# alphanewt_v1_3.net
KiCad netlist of a schematic drawn in EAGLE
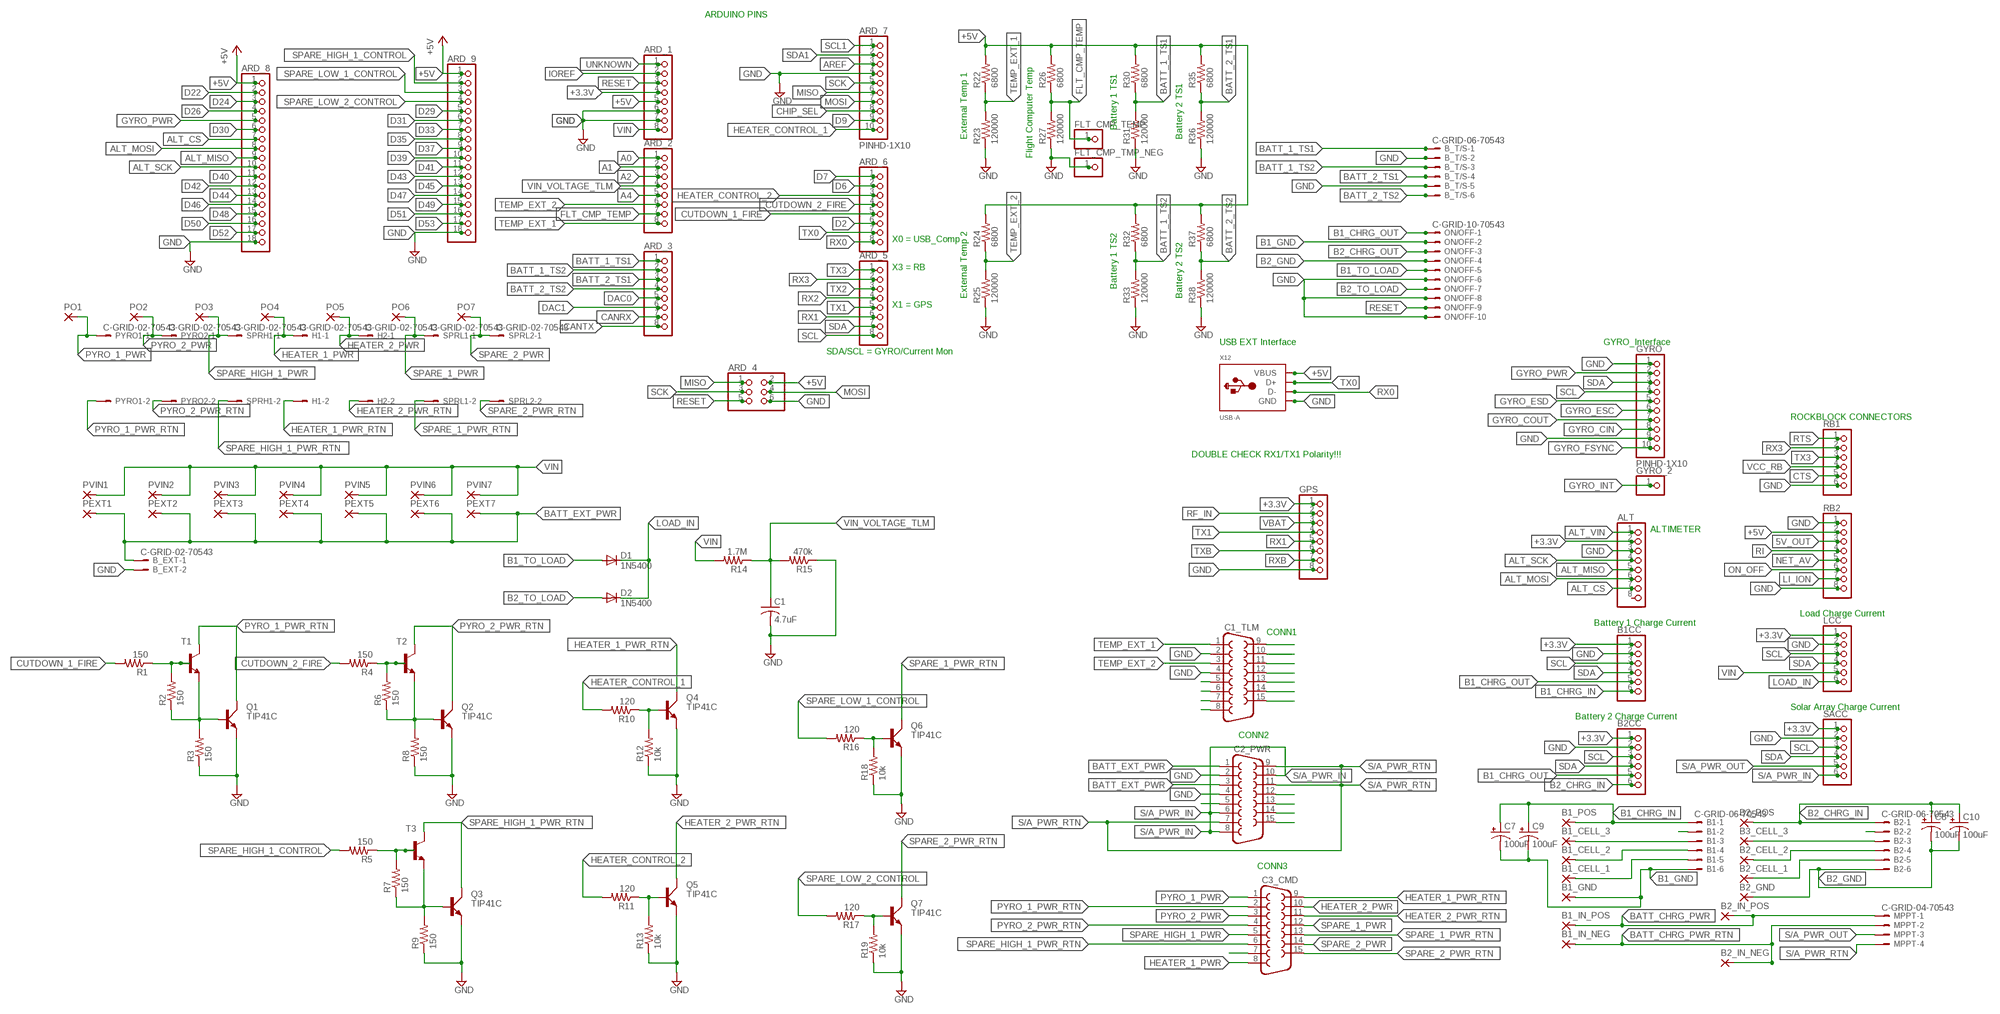
[diagram p0: schematic, sheet 1]

(export (version "E")
  (design (tool "Eeschema 10.0.6"))
  (components
    (comp (ref "ALT")
      (value "PINHD-1X8BIG")
      (footprint "eagle-import:1X08-BIG")
      (libsource (lib "eagle-import") (part "PINHD-1X8BIG"))
    )
    (comp (ref "ARD_1")
      (value "PINHD-1X8BIG")
      (footprint "eagle-import:1X08-BIG")
      (libsource (lib "eagle-import") (part "PINHD-1X8BIG"))
    )
    (comp (ref "ARD_2")
      (value "PINHD-1X8BIG")
      (footprint "eagle-import:1X08-BIG")
      (libsource (lib "eagle-import") (part "PINHD-1X8BIG"))
    )
    (comp (ref "ARD_3")
      (value "PINHD-1X8BIG")
      (footprint "eagle-import:1X08-BIG")
      (libsource (lib "eagle-import") (part "PINHD-1X8BIG"))
    )
    (comp (ref "ARD_4")
      (value "PINHD-2X3")
      (footprint "eagle-import:2X03")
      (libsource (lib "eagle-import") (part "PINHD-2X3"))
    )
    (comp (ref "ARD_5")
      (value "PINHD-1X8BIG")
      (footprint "eagle-import:1X08-BIG")
      (libsource (lib "eagle-import") (part "PINHD-1X8BIG"))
    )
    (comp (ref "ARD_6")
      (value "PINHD-1X8BIG")
      (footprint "eagle-import:1X08-BIG")
      (libsource (lib "eagle-import") (part "PINHD-1X8BIG"))
    )
    (comp (ref "ARD_7")
      (value "PINHD-1X10")
      (footprint "eagle-import:1X10-BIG")
      (libsource (lib "eagle-import") (part "PINHD-1X10"))
    )
    (comp (ref "ARD_8")
      (value "PINHD-1X18-BIG")
      (footprint "eagle-import:1X18-BIG")
      (libsource (lib "eagle-import") (part "PINHD-1X18-BIG"))
    )
    (comp (ref "ARD_9")
      (value "PINHD-1X18-BIG")
      (footprint "eagle-import:1X18-BIG")
      (libsource (lib "eagle-import") (part "PINHD-1X18-BIG"))
    )
    (comp (ref "B1")
      (value "C-GRID-06-70543")
      (footprint "eagle-import:70543-06")
      (fields
        (field (name "MF") "MOLEX")
        (field (name "MPN") "70543-0005")
        (field (name "OC_NEWARK") "59H2647")
      )
      (libsource (lib "eagle-import") (part "C-GRID-06-70543"))
    )
    (comp (ref "B1CC")
      (value "PINHD-1X6B")
      (footprint "eagle-import:1X06-BIG")
      (libsource (lib "eagle-import") (part "PINHD-1X6B"))
    )
    (comp (ref "B1_CELL_1")
      (value "SMD5")
      (footprint "eagle-import:SMD2,54-5,08")
      (libsource (lib "eagle-import") (part "SMD5"))
    )
    (comp (ref "B1_CELL_2")
      (value "SMD5")
      (footprint "eagle-import:SMD2,54-5,08")
      (libsource (lib "eagle-import") (part "SMD5"))
    )
    (comp (ref "B1_CELL_3")
      (value "SMD5")
      (footprint "eagle-import:SMD2,54-5,08")
      (libsource (lib "eagle-import") (part "SMD5"))
    )
    (comp (ref "B1_GND")
      (value "SMD5")
      (footprint "eagle-import:SMD2,54-5,08")
      (libsource (lib "eagle-import") (part "SMD5"))
    )
    (comp (ref "B1_IN_NEG")
      (value "SMD5")
      (footprint "eagle-import:SMD2,54-5,08")
      (libsource (lib "eagle-import") (part "SMD5"))
    )
    (comp (ref "B1_IN_POS")
      (value "SMD5")
      (footprint "eagle-import:SMD2,54-5,08")
      (libsource (lib "eagle-import") (part "SMD5"))
    )
    (comp (ref "B1_POS")
      (value "SMD5")
      (footprint "eagle-import:SMD2,54-5,08")
      (libsource (lib "eagle-import") (part "SMD5"))
    )
    (comp (ref "B2")
      (value "C-GRID-06-70543")
      (footprint "eagle-import:70543-06")
      (fields
        (field (name "MF") "MOLEX")
        (field (name "MPN") "70543-0005")
        (field (name "OC_NEWARK") "59H2647")
      )
      (libsource (lib "eagle-import") (part "C-GRID-06-70543"))
    )
    (comp (ref "B2CC")
      (value "PINHD-1X6B")
      (footprint "eagle-import:1X06-BIG")
      (libsource (lib "eagle-import") (part "PINHD-1X6B"))
    )
    (comp (ref "B2_CELL_1")
      (value "SMD5")
      (footprint "eagle-import:SMD2,54-5,08")
      (libsource (lib "eagle-import") (part "SMD5"))
    )
    (comp (ref "B2_CELL_2")
      (value "SMD5")
      (footprint "eagle-import:SMD2,54-5,08")
      (libsource (lib "eagle-import") (part "SMD5"))
    )
    (comp (ref "B2_GND")
      (value "SMD5")
      (footprint "eagle-import:SMD2,54-5,08")
      (libsource (lib "eagle-import") (part "SMD5"))
    )
    (comp (ref "B2_IN_NEG")
      (value "SMD5")
      (footprint "eagle-import:SMD2,54-5,08")
      (libsource (lib "eagle-import") (part "SMD5"))
    )
    (comp (ref "B2_IN_POS")
      (value "SMD5")
      (footprint "eagle-import:SMD2,54-5,08")
      (libsource (lib "eagle-import") (part "SMD5"))
    )
    (comp (ref "B2_POS")
      (value "SMD5")
      (footprint "eagle-import:SMD2,54-5,08")
      (libsource (lib "eagle-import") (part "SMD5"))
    )
    (comp (ref "B3_CELL_3")
      (value "SMD5")
      (footprint "eagle-import:SMD2,54-5,08")
      (libsource (lib "eagle-import") (part "SMD5"))
    )
    (comp (ref "B_EXT")
      (value "C-GRID-02-70543")
      (footprint "eagle-import:70543-02")
      (fields
        (field (name "MF") "MOLEX")
        (field (name "MPN") "70543-0001")
        (field (name "OC_NEWARK") "59H2645")
      )
      (libsource (lib "eagle-import") (part "C-GRID-02-70543"))
    )
    (comp (ref "B_T/S")
      (value "C-GRID-06-70543")
      (footprint "eagle-import:70543-06")
      (fields
        (field (name "MF") "MOLEX")
        (field (name "MPN") "70543-0005")
        (field (name "OC_NEWARK") "59H2647")
      )
      (libsource (lib "eagle-import") (part "C-GRID-06-70543"))
    )
    (comp (ref "C1")
      (value "4.7uF")
      (footprint "eagle-import:C0805K")
      (fields (field (name "MPN") "C2012X6S1H475K125AC"))
      (libsource (lib "eagle-import") (part "C-USC0805K"))
    )
    (comp (ref "C1_TLM")
      (value "F15HP")
      (footprint "eagle-import:F15HP")
      (fields (field (name "MPN") "5504F1-15S-02A-03"))
      (libsource (lib "eagle-import") (part "F15HP"))
    )
    (comp (ref "C2_PWR")
      (value "F15HP")
      (footprint "eagle-import:F15HP")
      (fields (field (name "MPN") "5504F1-15S-02A-03"))
      (libsource (lib "eagle-import") (part "F15HP"))
    )
    (comp (ref "C3_CMD")
      (value "F15HP")
      (footprint "eagle-import:F15HP")
      (fields (field (name "MPN") "5504F1-15S-02A-03"))
      (libsource (lib "eagle-import") (part "F15HP"))
    )
    (comp (ref "C7")
      (value "100uF")
      (footprint "eagle-import:CT7343")
      (fields (field (name "MPN") "TCN4337M020R0100"))
      (libsource (lib "eagle-import") (part "CPOL-USCT7343"))
    )
    (comp (ref "C8")
      (value "100uF")
      (footprint "eagle-import:CT7343")
      (fields (field (name "MPN") "TCN4337M020R0100"))
      (libsource (lib "eagle-import") (part "CPOL-USCT7343"))
    )
    (comp (ref "C9")
      (value "100uF")
      (footprint "eagle-import:CT7343")
      (fields (field (name "MPN") "TCN4337M020R0100"))
      (libsource (lib "eagle-import") (part "CPOL-USCT7343"))
    )
    (comp (ref "C10")
      (value "100uF")
      (footprint "eagle-import:CT7343")
      (fields (field (name "MPN") "TCN4337M020R0100"))
      (libsource (lib "eagle-import") (part "CPOL-USCT7343"))
    )
    (comp (ref "D1")
      (value "1N5400")
      (footprint "eagle-import:DO201-15")
      (fields (field (name "MPN") "1N5400-E3/54"))
      (libsource (lib "eagle-import") (part "1N5400"))
    )
    (comp (ref "D2")
      (value "1N5400")
      (footprint "eagle-import:DO201-15")
      (fields (field (name "MPN") "1N5400-E3/54"))
      (libsource (lib "eagle-import") (part "1N5400"))
    )
    (comp (ref "FLT_CMP_TEMP")
      (value "PINHD-1X1")
      (footprint "eagle-import:1X01")
      (libsource (lib "eagle-import") (part "PINHD-1X1"))
    )
    (comp (ref "FLT_CMP_TMP_NEG")
      (value "PINHD-1X1")
      (footprint "eagle-import:1X01")
      (libsource (lib "eagle-import") (part "PINHD-1X1"))
    )
    (comp (ref "GPS")
      (value "PINHD-1X8BIG")
      (footprint "eagle-import:1X08-BIG")
      (libsource (lib "eagle-import") (part "PINHD-1X8BIG"))
    )
    (comp (ref "GYRO")
      (value "PINHD-1X10")
      (footprint "eagle-import:1X10-BIG")
      (libsource (lib "eagle-import") (part "PINHD-1X10"))
    )
    (comp (ref "GYRO_2")
      (value "PINHD-1X1")
      (footprint "eagle-import:1X01")
      (libsource (lib "eagle-import") (part "PINHD-1X1"))
    )
    (comp (ref "H1")
      (value "C-GRID-02-70543")
      (footprint "eagle-import:70543-02")
      (fields
        (field (name "MF") "MOLEX")
        (field (name "MPN") "70543-0001")
        (field (name "OC_NEWARK") "59H2645")
      )
      (libsource (lib "eagle-import") (part "C-GRID-02-70543"))
    )
    (comp (ref "H2")
      (value "C-GRID-02-70543")
      (footprint "eagle-import:70543-02")
      (fields
        (field (name "MF") "MOLEX")
        (field (name "MPN") "70543-0001")
        (field (name "OC_NEWARK") "59H2645")
      )
      (libsource (lib "eagle-import") (part "C-GRID-02-70543"))
    )
    (comp (ref "LCC")
      (value "PINHD-1X6B")
      (footprint "eagle-import:1X06-BIG")
      (libsource (lib "eagle-import") (part "PINHD-1X6B"))
    )
    (comp (ref "MPPT")
      (value "C-GRID-04-70543")
      (footprint "eagle-import:70543-04")
      (fields
        (field (name "MF") "MOLEX")
        (field (name "MPN") "70543-0038")
        (field (name "OC_NEWARK") "59H2665")
      )
      (libsource (lib "eagle-import") (part "C-GRID-04-70543"))
    )
    (comp (ref "ON/OFF")
      (value "C-GRID-10-70543")
      (footprint "eagle-import:70543-10")
      (fields
        (field (name "MF") "MOLEX")
        (field (name "MPN") "70543-0009")
        (field (name "OC_NEWARK") "59H2651")
      )
      (libsource (lib "eagle-import") (part "C-GRID-10-70543"))
    )
    (comp (ref "PEXT1")
      (value "SMD2")
      (footprint "eagle-import:SMD1,27-2,54")
      (libsource (lib "eagle-import") (part "SMD2"))
    )
    (comp (ref "PEXT2")
      (value "SMD2")
      (footprint "eagle-import:SMD1,27-2,54")
      (libsource (lib "eagle-import") (part "SMD2"))
    )
    (comp (ref "PEXT3")
      (value "SMD2")
      (footprint "eagle-import:SMD1,27-2,54")
      (libsource (lib "eagle-import") (part "SMD2"))
    )
    (comp (ref "PEXT4")
      (value "SMD2")
      (footprint "eagle-import:SMD1,27-2,54")
      (libsource (lib "eagle-import") (part "SMD2"))
    )
    (comp (ref "PEXT5")
      (value "SMD2")
      (footprint "eagle-import:SMD1,27-2,54")
      (libsource (lib "eagle-import") (part "SMD2"))
    )
    (comp (ref "PEXT6")
      (value "SMD2")
      (footprint "eagle-import:SMD1,27-2,54")
      (libsource (lib "eagle-import") (part "SMD2"))
    )
    (comp (ref "PEXT7")
      (value "SMD2")
      (footprint "eagle-import:SMD1,27-2,54")
      (libsource (lib "eagle-import") (part "SMD2"))
    )
    (comp (ref "PO1")
      (value "SMD2")
      (footprint "eagle-import:SMD1,27-2,54")
      (libsource (lib "eagle-import") (part "SMD2"))
    )
    (comp (ref "PO2")
      (value "SMD2")
      (footprint "eagle-import:SMD1,27-2,54")
      (libsource (lib "eagle-import") (part "SMD2"))
    )
    (comp (ref "PO3")
      (value "SMD2")
      (footprint "eagle-import:SMD1,27-2,54")
      (libsource (lib "eagle-import") (part "SMD2"))
    )
    (comp (ref "PO4")
      (value "SMD2")
      (footprint "eagle-import:SMD1,27-2,54")
      (libsource (lib "eagle-import") (part "SMD2"))
    )
    (comp (ref "PO5")
      (value "SMD2")
      (footprint "eagle-import:SMD1,27-2,54")
      (libsource (lib "eagle-import") (part "SMD2"))
    )
    (comp (ref "PO6")
      (value "SMD2")
      (footprint "eagle-import:SMD1,27-2,54")
      (libsource (lib "eagle-import") (part "SMD2"))
    )
    (comp (ref "PO7")
      (value "SMD2")
      (footprint "eagle-import:SMD1,27-2,54")
      (libsource (lib "eagle-import") (part "SMD2"))
    )
    (comp (ref "PVIN1")
      (value "SMD2")
      (footprint "eagle-import:SMD1,27-2,54")
      (libsource (lib "eagle-import") (part "SMD2"))
    )
    (comp (ref "PVIN2")
      (value "SMD2")
      (footprint "eagle-import:SMD1,27-2,54")
      (libsource (lib "eagle-import") (part "SMD2"))
    )
    (comp (ref "PVIN3")
      (value "SMD2")
      (footprint "eagle-import:SMD1,27-2,54")
      (libsource (lib "eagle-import") (part "SMD2"))
    )
    (comp (ref "PVIN4")
      (value "SMD2")
      (footprint "eagle-import:SMD1,27-2,54")
      (libsource (lib "eagle-import") (part "SMD2"))
    )
    (comp (ref "PVIN5")
      (value "SMD2")
      (footprint "eagle-import:SMD1,27-2,54")
      (libsource (lib "eagle-import") (part "SMD2"))
    )
    (comp (ref "PVIN6")
      (value "SMD2")
      (footprint "eagle-import:SMD1,27-2,54")
      (libsource (lib "eagle-import") (part "SMD2"))
    )
    (comp (ref "PVIN7")
      (value "SMD2")
      (footprint "eagle-import:SMD1,27-2,54")
      (libsource (lib "eagle-import") (part "SMD2"))
    )
    (comp (ref "PYRO1")
      (value "C-GRID-02-70543")
      (footprint "eagle-import:70543-02")
      (fields
        (field (name "MF") "MOLEX")
        (field (name "MPN") "70543-0001")
        (field (name "OC_NEWARK") "59H2645")
      )
      (libsource (lib "eagle-import") (part "C-GRID-02-70543"))
    )
    (comp (ref "PYRO2")
      (value "C-GRID-02-70543")
      (footprint "eagle-import:70543-02")
      (fields
        (field (name "MF") "MOLEX")
        (field (name "MPN") "70543-0001")
        (field (name "OC_NEWARK") "59H2645")
      )
      (libsource (lib "eagle-import") (part "C-GRID-02-70543"))
    )
    (comp (ref "Q1")
      (value "TIP41C")
      (footprint "eagle-import:TO220AV")
      (fields (field (name "MF") "FAIRCHILD SEMICONDUCTOR"))
      (libsource (lib "eagle-import") (part "TIP41C"))
    )
    (comp (ref "Q2")
      (value "TIP41C")
      (footprint "eagle-import:TO220AV")
      (fields (field (name "MF") "FAIRCHILD SEMICONDUCTOR"))
      (libsource (lib "eagle-import") (part "TIP41C"))
    )
    (comp (ref "Q3")
      (value "TIP41C")
      (footprint "eagle-import:TO220AV")
      (fields (field (name "MF") "FAIRCHILD SEMICONDUCTOR"))
      (libsource (lib "eagle-import") (part "TIP41C"))
    )
    (comp (ref "Q4")
      (value "TIP41C")
      (footprint "eagle-import:TO220AV")
      (fields (field (name "MF") "FAIRCHILD SEMICONDUCTOR"))
      (libsource (lib "eagle-import") (part "TIP41C"))
    )
    (comp (ref "Q5")
      (value "TIP41C")
      (footprint "eagle-import:TO220AV")
      (fields (field (name "MF") "FAIRCHILD SEMICONDUCTOR"))
      (libsource (lib "eagle-import") (part "TIP41C"))
    )
    (comp (ref "Q6")
      (value "TIP41C")
      (footprint "eagle-import:TO220AV")
      (fields (field (name "MF") "FAIRCHILD SEMICONDUCTOR"))
      (libsource (lib "eagle-import") (part "TIP41C"))
    )
    (comp (ref "Q7")
      (value "TIP41C")
      (footprint "eagle-import:TO220AV")
      (fields (field (name "MF") "FAIRCHILD SEMICONDUCTOR"))
      (libsource (lib "eagle-import") (part "TIP41C"))
    )
    (comp (ref "R1")
      (value "150")
      (footprint "eagle-import:R0805")
      (fields (field (name "MF") "VISHAY/DALE") (field (name "MPN") "CRCW120633R2FKEA"))
      (libsource (lib "eagle-import") (part "R-US_R0805"))
    )
    (comp (ref "R2")
      (value "150")
      (footprint "eagle-import:R0805")
      (fields (field (name "MF") "VISHAY/DALE") (field (name "MPN") "CRCW120633R2FKEA"))
      (libsource (lib "eagle-import") (part "R-US_R0805"))
    )
    (comp (ref "R3")
      (value "150")
      (footprint "eagle-import:R0805")
      (fields (field (name "MF") "VISHAY/DALE") (field (name "MPN") "CRCW120633R2FKEA"))
      (libsource (lib "eagle-import") (part "R-US_R0805"))
    )
    (comp (ref "R4")
      (value "150")
      (footprint "eagle-import:R0805")
      (fields (field (name "MF") "VISHAY/DALE") (field (name "MPN") "CRCW120633R2FKEA"))
      (libsource (lib "eagle-import") (part "R-US_R0805"))
    )
    (comp (ref "R5")
      (value "150")
      (footprint "eagle-import:R0805")
      (fields (field (name "MF") "VISHAY/DALE") (field (name "MPN") "CRCW120633R2FKEA"))
      (libsource (lib "eagle-import") (part "R-US_R0805"))
    )
    (comp (ref "R6")
      (value "150")
      (footprint "eagle-import:R0805")
      (fields (field (name "MF") "VISHAY/DALE") (field (name "MPN") "CRCW120633R2FKEA"))
      (libsource (lib "eagle-import") (part "R-US_R0805"))
    )
    (comp (ref "R7")
      (value "150")
      (footprint "eagle-import:R0805")
      (fields (field (name "MF") "VISHAY/DALE") (field (name "MPN") "CRCW120633R2FKEA"))
      (libsource (lib "eagle-import") (part "R-US_R0805"))
    )
    (comp (ref "R8")
      (value "150")
      (footprint "eagle-import:R0805")
      (fields (field (name "MF") "VISHAY/DALE") (field (name "MPN") "CRCW120633R2FKEA"))
      (libsource (lib "eagle-import") (part "R-US_R0805"))
    )
    (comp (ref "R9")
      (value "150")
      (footprint "eagle-import:R0805")
      (fields (field (name "MF") "VISHAY/DALE") (field (name "MPN") "CRCW120633R2FKEA"))
      (libsource (lib "eagle-import") (part "R-US_R0805"))
    )
    (comp (ref "R10")
      (value "120")
      (footprint "eagle-import:R0805")
      (fields (field (name "MF") "VISHAY/DALE") (field (name "MPN") "CRCW120633R2FKEA"))
      (libsource (lib "eagle-import") (part "R-US_R0805"))
    )
    (comp (ref "R11")
      (value "120")
      (footprint "eagle-import:R0805")
      (fields (field (name "MF") "VISHAY/DALE") (field (name "MPN") "CRCW120633R2FKEA"))
      (libsource (lib "eagle-import") (part "R-US_R0805"))
    )
    (comp (ref "R12")
      (value "10k")
      (footprint "eagle-import:R0805")
      (fields (field (name "MF") "VISHAY/DALE") (field (name "MPN") "CRCW120633R2FKEA"))
      (libsource (lib "eagle-import") (part "R-US_R0805"))
    )
    (comp (ref "R13")
      (value "10k")
      (footprint "eagle-import:R0805")
      (fields (field (name "MF") "VISHAY/DALE") (field (name "MPN") "CRCW120633R2FKEA"))
      (libsource (lib "eagle-import") (part "R-US_R0805"))
    )
    (comp (ref "R14")
      (value "1.7M")
      (footprint "eagle-import:R0805")
      (fields (field (name "MF") "VISHAY/DALE") (field (name "MPN") "CRCW120633R2FKEA"))
      (libsource (lib "eagle-import") (part "R-US_R0805"))
    )
    (comp (ref "R15")
      (value "470k")
      (footprint "eagle-import:R0805")
      (fields (field (name "MF") "VISHAY/DALE") (field (name "MPN") "CRCW120633R2FKEA"))
      (libsource (lib "eagle-import") (part "R-US_R0805"))
    )
    (comp (ref "R16")
      (value "120")
      (footprint "eagle-import:R0805")
      (fields (field (name "MF") "VISHAY/DALE") (field (name "MPN") "CRCW120633R2FKEA"))
      (libsource (lib "eagle-import") (part "R-US_R0805"))
    )
    (comp (ref "R17")
      (value "120")
      (footprint "eagle-import:R0805")
      (fields (field (name "MF") "VISHAY/DALE") (field (name "MPN") "CRCW120633R2FKEA"))
      (libsource (lib "eagle-import") (part "R-US_R0805"))
    )
    (comp (ref "R18")
      (value "10k")
      (footprint "eagle-import:R0805")
      (fields (field (name "MF") "VISHAY/DALE") (field (name "MPN") "CRCW120633R2FKEA"))
      (libsource (lib "eagle-import") (part "R-US_R0805"))
    )
    (comp (ref "R19")
      (value "10k")
      (footprint "eagle-import:R0805")
      (fields (field (name "MF") "VISHAY/DALE") (field (name "MPN") "CRCW120633R2FKEA"))
      (libsource (lib "eagle-import") (part "R-US_R0805"))
    )
    (comp (ref "R22")
      (value "6800")
      (footprint "eagle-import:R0805")
      (fields (field (name "MF") "VISHAY/DALE") (field (name "MPN") "CRCW120633R2FKEA"))
      (libsource (lib "eagle-import") (part "R-US_R0805"))
    )
    (comp (ref "R23")
      (value "120000")
      (footprint "eagle-import:R0805")
      (fields (field (name "MF") "VISHAY/DALE") (field (name "MPN") "CRCW120633R2FKEA"))
      (libsource (lib "eagle-import") (part "R-US_R0805"))
    )
    (comp (ref "R24")
      (value "6800")
      (footprint "eagle-import:R0805")
      (fields (field (name "MF") "VISHAY/DALE") (field (name "MPN") "CRCW120633R2FKEA"))
      (libsource (lib "eagle-import") (part "R-US_R0805"))
    )
    (comp (ref "R25")
      (value "120000")
      (footprint "eagle-import:R0805")
      (fields (field (name "MF") "VISHAY/DALE") (field (name "MPN") "CRCW120633R2FKEA"))
      (libsource (lib "eagle-import") (part "R-US_R0805"))
    )
    (comp (ref "R26")
      (value "6800")
      (footprint "eagle-import:R0805")
      (fields (field (name "MF") "VISHAY/DALE") (field (name "MPN") "CRCW120633R2FKEA"))
      (libsource (lib "eagle-import") (part "R-US_R0805"))
    )
    (comp (ref "R27")
      (value "120000")
      (footprint "eagle-import:R0805")
      (fields (field (name "MF") "VISHAY/DALE") (field (name "MPN") "CRCW120633R2FKEA"))
      (libsource (lib "eagle-import") (part "R-US_R0805"))
    )
    (comp (ref "R30")
      (value "6800")
      (footprint "eagle-import:R0805")
      (fields (field (name "MF") "VISHAY/DALE") (field (name "MPN") "CRCW120633R2FKEA"))
      (libsource (lib "eagle-import") (part "R-US_R0805"))
    )
    (comp (ref "R31")
      (value "120000")
      (footprint "eagle-import:R0805")
      (fields (field (name "MF") "VISHAY/DALE") (field (name "MPN") "CRCW120633R2FKEA"))
      (libsource (lib "eagle-import") (part "R-US_R0805"))
    )
    (comp (ref "R32")
      (value "6800")
      (footprint "eagle-import:R0805")
      (fields (field (name "MF") "VISHAY/DALE") (field (name "MPN") "CRCW120633R2FKEA"))
      (libsource (lib "eagle-import") (part "R-US_R0805"))
    )
    (comp (ref "R33")
      (value "120000")
      (footprint "eagle-import:R0805")
      (fields (field (name "MF") "VISHAY/DALE") (field (name "MPN") "CRCW120633R2FKEA"))
      (libsource (lib "eagle-import") (part "R-US_R0805"))
    )
    (comp (ref "R35")
      (value "6800")
      (footprint "eagle-import:R0805")
      (fields (field (name "MF") "VISHAY/DALE") (field (name "MPN") "CRCW120633R2FKEA"))
      (libsource (lib "eagle-import") (part "R-US_R0805"))
    )
    (comp (ref "R36")
      (value "120000")
      (footprint "eagle-import:R0805")
      (fields (field (name "MF") "VISHAY/DALE") (field (name "MPN") "CRCW120633R2FKEA"))
      (libsource (lib "eagle-import") (part "R-US_R0805"))
    )
    (comp (ref "R37")
      (value "6800")
      (footprint "eagle-import:R0805")
      (fields (field (name "MF") "VISHAY/DALE") (field (name "MPN") "CRCW120633R2FKEA"))
      (libsource (lib "eagle-import") (part "R-US_R0805"))
    )
    (comp (ref "R38")
      (value "120000")
      (footprint "eagle-import:R0805")
      (fields (field (name "MF") "VISHAY/DALE") (field (name "MPN") "CRCW120633R2FKEA"))
      (libsource (lib "eagle-import") (part "R-US_R0805"))
    )
    (comp (ref "RB1")
      (value "PINHD-1X6CB")
      (footprint "eagle-import:1X06-CLEANBIG")
      (libsource (lib "eagle-import") (part "PINHD-1X6CB"))
    )
    (comp (ref "RB2")
      (value "PINHD-1X8BIG")
      (footprint "eagle-import:1X08-BIG")
      (libsource (lib "eagle-import") (part "PINHD-1X8BIG"))
    )
    (comp (ref "SACC")
      (value "PINHD-1X6B")
      (footprint "eagle-import:1X06-BIG")
      (libsource (lib "eagle-import") (part "PINHD-1X6B"))
    )
    (comp (ref "SPRH1")
      (value "C-GRID-02-70543")
      (footprint "eagle-import:70543-02")
      (fields
        (field (name "MF") "MOLEX")
        (field (name "MPN") "70543-0001")
        (field (name "OC_NEWARK") "59H2645")
      )
      (libsource (lib "eagle-import") (part "C-GRID-02-70543"))
    )
    (comp (ref "SPRL1")
      (value "C-GRID-02-70543")
      (footprint "eagle-import:70543-02")
      (fields
        (field (name "MF") "MOLEX")
        (field (name "MPN") "70543-0001")
        (field (name "OC_NEWARK") "59H2645")
      )
      (libsource (lib "eagle-import") (part "C-GRID-02-70543"))
    )
    (comp (ref "SPRL2")
      (value "C-GRID-02-70543")
      (footprint "eagle-import:70543-02")
      (fields
        (field (name "MF") "MOLEX")
        (field (name "MPN") "70543-0001")
        (field (name "OC_NEWARK") "59H2645")
      )
      (libsource (lib "eagle-import") (part "C-GRID-02-70543"))
    )
    (comp (ref "T1")
      (value "2N3904")
      (footprint "eagle-import:TO92")
      (fields (field (name "MF") "NTE ELECTRONICS"))
      (libsource (lib "eagle-import") (part "2N3904"))
    )
    (comp (ref "T2")
      (value "2N3904")
      (footprint "eagle-import:TO92")
      (fields (field (name "MF") "NTE ELECTRONICS"))
      (libsource (lib "eagle-import") (part "2N3904"))
    )
    (comp (ref "T3")
      (value "2N3904")
      (footprint "eagle-import:TO92")
      (fields (field (name "MF") "NTE ELECTRONICS"))
      (libsource (lib "eagle-import") (part "2N3904"))
    )
    (comp (ref "X12")
      (value "USB-A")
      (footprint "eagle-import:MOLEX_480371000")
      (fields (field (name "MPN") "UE27-AC54-10H"))
      (libsource (lib "eagle-import") (part "USB-A"))
    )
  )
  (nets
    (net (code "1") (name "+3.3V") (class "Default")
      (node (ref "ALT") (pin "2") (pinfunction "2_2") (pintype "passive"))
      (node (ref "ARD_1") (pin "4") (pinfunction "4_4") (pintype "passive"))
      (node (ref "B1CC") (pin "1") (pinfunction "1_1") (pintype "passive"))
      (node (ref "B2CC") (pin "1") (pinfunction "1_1") (pintype "passive"))
      (node (ref "GPS") (pin "1") (pinfunction "1_1") (pintype "passive"))
      (node (ref "LCC") (pin "1") (pinfunction "1_1") (pintype "passive"))
      (node (ref "SACC") (pin "1") (pinfunction "1_1") (pintype "passive"))
    )
    (net (code "2") (name "+5V") (class "Default")
      (node (ref "ARD_1") (pin "5") (pinfunction "5_5") (pintype "passive"))
      (node (ref "ARD_4") (pin "2") (pinfunction "2_2") (pintype "passive"))
      (node (ref "ARD_8") (pin "1") (pinfunction "1_1") (pintype "passive"))
      (node (ref "ARD_9") (pin "1") (pinfunction "1_1") (pintype "passive"))
      (node (ref "R22") (pin "2") (pinfunction "2_2") (pintype "passive"))
      (node (ref "R24") (pin "2") (pinfunction "2_2") (pintype "passive"))
      (node (ref "R26") (pin "2") (pinfunction "2_2") (pintype "passive"))
      (node (ref "R30") (pin "2") (pinfunction "2_2") (pintype "passive"))
      (node (ref "R32") (pin "2") (pinfunction "2_2") (pintype "passive"))
      (node (ref "R35") (pin "2") (pinfunction "2_2") (pintype "passive"))
      (node (ref "R37") (pin "2") (pinfunction "2_2") (pintype "passive"))
      (node (ref "RB2") (pin "2") (pinfunction "2_2") (pintype "passive"))
      (node (ref "X12") (pin "1") (pinfunction "VBUS_1") (pintype "power_in"))
    )
    (net (code "3") (name "5V_OUT") (class "Default")
      (node (ref "RB2") (pin "3") (pinfunction "3_3") (pintype "passive"))
    )
    (net (code "4") (name "A0") (class "Default")
      (node (ref "ARD_2") (pin "1") (pinfunction "1_1") (pintype "passive"))
    )
    (net (code "5") (name "A1") (class "Default")
      (node (ref "ARD_2") (pin "2") (pinfunction "2_2") (pintype "passive"))
    )
    (net (code "6") (name "A2") (class "Default")
      (node (ref "ARD_2") (pin "3") (pinfunction "3_3") (pintype "passive"))
    )
    (net (code "7") (name "A4") (class "Default")
      (node (ref "ARD_2") (pin "5") (pinfunction "5_5") (pintype "passive"))
    )
    (net (code "8") (name "ALT_CS") (class "Default")
      (node (ref "ALT") (pin "7") (pinfunction "7_7") (pintype "passive"))
      (node (ref "ARD_8") (pin "7") (pinfunction "7_7") (pintype "passive"))
    )
    (net (code "9") (name "ALT_MISO") (class "Default")
      (node (ref "ALT") (pin "5") (pinfunction "5_5") (pintype "passive"))
      (node (ref "ARD_8") (pin "9") (pinfunction "9_9") (pintype "passive"))
    )
    (net (code "10") (name "ALT_MOSI") (class "Default")
      (node (ref "ALT") (pin "6") (pinfunction "6_6") (pintype "passive"))
      (node (ref "ARD_8") (pin "8") (pinfunction "8_8") (pintype "passive"))
    )
    (net (code "11") (name "ALT_SCK") (class "Default")
      (node (ref "ALT") (pin "4") (pinfunction "4_4") (pintype "passive"))
      (node (ref "ARD_8") (pin "10") (pinfunction "10_10") (pintype "passive"))
    )
    (net (code "12") (name "ALT_VIN") (class "Default")
      (node (ref "ALT") (pin "1") (pinfunction "1_1") (pintype "passive"))
    )
    (net (code "13") (name "AREF") (class "Default")
      (node (ref "ARD_7") (pin "3") (pinfunction "3_3") (pintype "passive"))
    )
    (net (code "14") (name "B1_CHRG_IN") (class "Default")
      (node (ref "B1") (pin "1") (pinfunction "S_1") (pintype "passive"))
      (node (ref "B1CC") (pin "6") (pinfunction "6_6") (pintype "passive"))
      (node (ref "B1_POS") (pin "1") (pinfunction "P_1") (pintype "passive"))
      (node (ref "C7") (pin "+") (pinfunction "+_+") (pintype "passive"))
      (node (ref "C9") (pin "+") (pinfunction "+_+") (pintype "passive"))
    )
    (net (code "15") (name "B1_CHRG_OUT") (class "Default")
      (node (ref "B1CC") (pin "5") (pinfunction "5_5") (pintype "passive"))
      (node (ref "B2CC") (pin "5") (pinfunction "5_5") (pintype "passive"))
      (node (ref "ON/OFF") (pin "1") (pinfunction "S_1") (pintype "passive"))
    )
    (net (code "16") (name "B1_GND") (class "Default")
      (node (ref "B1") (pin "6") (pinfunction "S_6") (pintype "passive"))
      (node (ref "B1_GND") (pin "1") (pinfunction "P_1") (pintype "passive"))
      (node (ref "C7") (pin "-") (pinfunction "-_-") (pintype "passive"))
      (node (ref "C9") (pin "-") (pinfunction "-_-") (pintype "passive"))
      (node (ref "ON/OFF") (pin "2") (pinfunction "S_2") (pintype "passive"))
    )
    (net (code "17") (name "B1_TO_LOAD") (class "Default")
      (node (ref "D1") (pin "A") (pinfunction "A_A") (pintype "passive"))
      (node (ref "ON/OFF") (pin "5") (pinfunction "S_5") (pintype "passive"))
    )
    (net (code "18") (name "B2_CHRG_IN") (class "Default")
      (node (ref "B2") (pin "1") (pinfunction "S_1") (pintype "passive"))
      (node (ref "B2CC") (pin "6") (pinfunction "6_6") (pintype "passive"))
      (node (ref "B2_POS") (pin "1") (pinfunction "P_1") (pintype "passive"))
      (node (ref "C10") (pin "+") (pinfunction "+_+") (pintype "passive"))
      (node (ref "C8") (pin "+") (pinfunction "+_+") (pintype "passive"))
    )
    (net (code "19") (name "B2_CHRG_OUT") (class "Default")
      (node (ref "ON/OFF") (pin "3") (pinfunction "S_3") (pintype "passive"))
    )
    (net (code "20") (name "B2_GND") (class "Default")
      (node (ref "B2") (pin "6") (pinfunction "S_6") (pintype "passive"))
      (node (ref "B2_GND") (pin "1") (pinfunction "P_1") (pintype "passive"))
      (node (ref "C10") (pin "-") (pinfunction "-_-") (pintype "passive"))
      (node (ref "C8") (pin "-") (pinfunction "-_-") (pintype "passive"))
      (node (ref "ON/OFF") (pin "4") (pinfunction "S_4") (pintype "passive"))
    )
    (net (code "21") (name "B2_TO_LOAD") (class "Default")
      (node (ref "D2") (pin "A") (pinfunction "A_A") (pintype "passive"))
      (node (ref "ON/OFF") (pin "7") (pinfunction "S_7") (pintype "passive"))
    )
    (net (code "22") (name "BATT_1_TS1") (class "Default")
      (node (ref "ARD_3") (pin "1") (pinfunction "1_1") (pintype "passive"))
      (node (ref "B_T/S") (pin "1") (pinfunction "S_1") (pintype "passive"))
      (node (ref "R30") (pin "1") (pinfunction "1_1") (pintype "passive"))
      (node (ref "R31") (pin "2") (pinfunction "2_2") (pintype "passive"))
    )
    (net (code "23") (name "BATT_1_TS2") (class "Default")
      (node (ref "ARD_3") (pin "2") (pinfunction "2_2") (pintype "passive"))
      (node (ref "B_T/S") (pin "3") (pinfunction "S_3") (pintype "passive"))
      (node (ref "R32") (pin "1") (pinfunction "1_1") (pintype "passive"))
      (node (ref "R33") (pin "2") (pinfunction "2_2") (pintype "passive"))
    )
    (net (code "24") (name "BATT_2_TS1") (class "Default")
      (node (ref "ARD_3") (pin "3") (pinfunction "3_3") (pintype "passive"))
      (node (ref "B_T/S") (pin "4") (pinfunction "S_4") (pintype "passive"))
      (node (ref "R35") (pin "1") (pinfunction "1_1") (pintype "passive"))
      (node (ref "R36") (pin "2") (pinfunction "2_2") (pintype "passive"))
    )
    (net (code "25") (name "BATT_2_TS2") (class "Default")
      (node (ref "ARD_3") (pin "4") (pinfunction "4_4") (pintype "passive"))
      (node (ref "B_T/S") (pin "6") (pinfunction "S_6") (pintype "passive"))
      (node (ref "R37") (pin "1") (pinfunction "1_1") (pintype "passive"))
      (node (ref "R38") (pin "2") (pinfunction "2_2") (pintype "passive"))
    )
    (net (code "26") (name "BATT_CHRG_PWR") (class "Default")
      (node (ref "B1_IN_POS") (pin "1") (pinfunction "P_1") (pintype "passive"))
      (node (ref "B2_IN_POS") (pin "1") (pinfunction "P_1") (pintype "passive"))
      (node (ref "MPPT") (pin "1") (pinfunction "S_1") (pintype "passive"))
    )
    (net (code "27") (name "BATT_CHRG_PWR_RTN") (class "Default")
      (node (ref "B1_IN_NEG") (pin "1") (pinfunction "P_1") (pintype "passive"))
      (node (ref "B2_IN_NEG") (pin "1") (pinfunction "P_1") (pintype "passive"))
      (node (ref "MPPT") (pin "2") (pinfunction "S_2") (pintype "passive"))
    )
    (net (code "28") (name "BATT_EXT_PWR") (class "Default")
      (node (ref "B_EXT") (pin "1") (pinfunction "S_1") (pintype "passive"))
      (node (ref "C2_PWR") (pin "1") (pinfunction "1_1") (pintype "passive"))
      (node (ref "C2_PWR") (pin "3") (pinfunction "3_3") (pintype "passive"))
      (node (ref "PEXT1") (pin "1") (pinfunction "P_1") (pintype "passive"))
      (node (ref "PEXT2") (pin "1") (pinfunction "P_1") (pintype "passive"))
      (node (ref "PEXT3") (pin "1") (pinfunction "P_1") (pintype "passive"))
      (node (ref "PEXT4") (pin "1") (pinfunction "P_1") (pintype "passive"))
      (node (ref "PEXT5") (pin "1") (pinfunction "P_1") (pintype "passive"))
      (node (ref "PEXT6") (pin "1") (pinfunction "P_1") (pintype "passive"))
      (node (ref "PEXT7") (pin "1") (pinfunction "P_1") (pintype "passive"))
    )
    (net (code "29") (name "CANRX") (class "Default")
      (node (ref "ARD_3") (pin "7") (pinfunction "7_7") (pintype "passive"))
    )
    (net (code "30") (name "CANTX") (class "Default")
      (node (ref "ARD_3") (pin "8") (pinfunction "8_8") (pintype "passive"))
    )
    (net (code "31") (name "CHIP_SEL") (class "Default")
      (node (ref "ARD_7") (pin "8") (pinfunction "8_8") (pintype "passive"))
    )
    (net (code "32") (name "CTS") (class "Default")
      (node (ref "RB1") (pin "5") (pinfunction "5_5") (pintype "passive"))
    )
    (net (code "33") (name "CUTDOWN_1_FIRE") (class "Default")
      (node (ref "ARD_6") (pin "5") (pinfunction "5_5") (pintype "passive"))
      (node (ref "R1") (pin "2") (pinfunction "2_2") (pintype "passive"))
    )
    (net (code "34") (name "CUTDOWN_2_FIRE") (class "Default")
      (node (ref "ARD_6") (pin "4") (pinfunction "4_4") (pintype "passive"))
      (node (ref "R4") (pin "2") (pinfunction "2_2") (pintype "passive"))
    )
    (net (code "35") (name "D2") (class "Default")
      (node (ref "ARD_6") (pin "6") (pinfunction "6_6") (pintype "passive"))
    )
    (net (code "36") (name "D6") (class "Default")
      (node (ref "ARD_6") (pin "2") (pinfunction "2_2") (pintype "passive"))
    )
    (net (code "37") (name "D7") (class "Default")
      (node (ref "ARD_6") (pin "1") (pinfunction "1_1") (pintype "passive"))
    )
    (net (code "38") (name "D9") (class "Default")
      (node (ref "ARD_7") (pin "9") (pinfunction "9_9") (pintype "passive"))
    )
    (net (code "39") (name "D22") (class "Default")
      (node (ref "ARD_8") (pin "2") (pinfunction "2_2") (pintype "passive"))
    )
    (net (code "40") (name "D24") (class "Default")
      (node (ref "ARD_8") (pin "3") (pinfunction "3_3") (pintype "passive"))
    )
    (net (code "41") (name "D26") (class "Default")
      (node (ref "ARD_8") (pin "4") (pinfunction "4_4") (pintype "passive"))
    )
    (net (code "42") (name "D29") (class "Default")
      (node (ref "ARD_9") (pin "5") (pinfunction "5_5") (pintype "passive"))
    )
    (net (code "43") (name "D30") (class "Default")
      (node (ref "ARD_8") (pin "6") (pinfunction "6_6") (pintype "passive"))
    )
    (net (code "44") (name "D31") (class "Default")
      (node (ref "ARD_9") (pin "6") (pinfunction "6_6") (pintype "passive"))
    )
    (net (code "45") (name "D33") (class "Default")
      (node (ref "ARD_9") (pin "7") (pinfunction "7_7") (pintype "passive"))
    )
    (net (code "46") (name "D35") (class "Default")
      (node (ref "ARD_9") (pin "8") (pinfunction "8_8") (pintype "passive"))
    )
    (net (code "47") (name "D37") (class "Default")
      (node (ref "ARD_9") (pin "9") (pinfunction "9_9") (pintype "passive"))
    )
    (net (code "48") (name "D39") (class "Default")
      (node (ref "ARD_9") (pin "10") (pinfunction "10_10") (pintype "passive"))
    )
    (net (code "49") (name "D40") (class "Default")
      (node (ref "ARD_8") (pin "11") (pinfunction "11_11") (pintype "passive"))
    )
    (net (code "50") (name "D41") (class "Default")
      (node (ref "ARD_9") (pin "11") (pinfunction "11_11") (pintype "passive"))
    )
    (net (code "51") (name "D42") (class "Default")
      (node (ref "ARD_8") (pin "12") (pinfunction "12_12") (pintype "passive"))
    )
    (net (code "52") (name "D43") (class "Default")
      (node (ref "ARD_9") (pin "12") (pinfunction "12_12") (pintype "passive"))
    )
    (net (code "53") (name "D44") (class "Default")
      (node (ref "ARD_8") (pin "13") (pinfunction "13_13") (pintype "passive"))
    )
    (net (code "54") (name "D45") (class "Default")
      (node (ref "ARD_9") (pin "13") (pinfunction "13_13") (pintype "passive"))
    )
    (net (code "55") (name "D46") (class "Default")
      (node (ref "ARD_8") (pin "14") (pinfunction "14_14") (pintype "passive"))
    )
    (net (code "56") (name "D47") (class "Default")
      (node (ref "ARD_9") (pin "14") (pinfunction "14_14") (pintype "passive"))
    )
    (net (code "57") (name "D48") (class "Default")
      (node (ref "ARD_8") (pin "15") (pinfunction "15_15") (pintype "passive"))
    )
    (net (code "58") (name "D49") (class "Default")
      (node (ref "ARD_9") (pin "15") (pinfunction "15_15") (pintype "passive"))
    )
    (net (code "59") (name "D50") (class "Default")
      (node (ref "ARD_8") (pin "16") (pinfunction "16_16") (pintype "passive"))
    )
    (net (code "60") (name "D51") (class "Default")
      (node (ref "ARD_9") (pin "16") (pinfunction "16_16") (pintype "passive"))
    )
    (net (code "61") (name "D52") (class "Default")
      (node (ref "ARD_8") (pin "17") (pinfunction "17_17") (pintype "passive"))
    )
    (net (code "62") (name "D53") (class "Default")
      (node (ref "ARD_9") (pin "17") (pinfunction "17_17") (pintype "passive"))
    )
    (net (code "63") (name "DAC0") (class "Default")
      (node (ref "ARD_3") (pin "5") (pinfunction "5_5") (pintype "passive"))
    )
    (net (code "64") (name "DAC1") (class "Default")
      (node (ref "ARD_3") (pin "6") (pinfunction "6_6") (pintype "passive"))
    )
    (net (code "65") (name "FLT_CMP_TEMP") (class "Default")
      (node (ref "ARD_2") (pin "7") (pinfunction "7_7") (pintype "passive"))
      (node (ref "FLT_CMP_TEMP") (pin "1") (pinfunction "1_1") (pintype "passive"))
      (node (ref "R26") (pin "1") (pinfunction "1_1") (pintype "passive"))
      (node (ref "R27") (pin "2") (pinfunction "2_2") (pintype "passive"))
    )
    (net (code "66") (name "GND") (class "Default")
      (node (ref "ALT") (pin "3") (pinfunction "3_3") (pintype "passive"))
      (node (ref "ARD_1") (pin "6") (pinfunction "6_6") (pintype "passive"))
      (node (ref "ARD_1") (pin "7") (pinfunction "7_7") (pintype "passive"))
      (node (ref "ARD_4") (pin "6") (pinfunction "6_6") (pintype "passive"))
      (node (ref "ARD_7") (pin "4") (pinfunction "4_4") (pintype "passive"))
      (node (ref "ARD_8") (pin "18") (pinfunction "18_18") (pintype "passive"))
      (node (ref "ARD_9") (pin "18") (pinfunction "18_18") (pintype "passive"))
      (node (ref "B1CC") (pin "2") (pinfunction "2_2") (pintype "passive"))
      (node (ref "B2CC") (pin "2") (pinfunction "2_2") (pintype "passive"))
      (node (ref "B_EXT") (pin "2") (pinfunction "S_2") (pintype "passive"))
      (node (ref "B_T/S") (pin "2") (pinfunction "S_2") (pintype "passive"))
      (node (ref "B_T/S") (pin "5") (pinfunction "S_5") (pintype "passive"))
      (node (ref "C1") (pin "2") (pinfunction "2_2") (pintype "passive"))
      (node (ref "C1_TLM") (pin "2") (pinfunction "2_2") (pintype "passive"))
      (node (ref "C1_TLM") (pin "4") (pinfunction "4_4") (pintype "passive"))
      (node (ref "C2_PWR") (pin "2") (pinfunction "2_2") (pintype "passive"))
      (node (ref "C2_PWR") (pin "4") (pinfunction "4_4") (pintype "passive"))
      (node (ref "FLT_CMP_TMP_NEG") (pin "1") (pinfunction "1_1") (pintype "passive"))
      (node (ref "GPS") (pin "8") (pinfunction "8_8") (pintype "passive"))
      (node (ref "GYRO") (pin "1") (pinfunction "1_1") (pintype "passive"))
      (node (ref "GYRO") (pin "9") (pinfunction "9_9") (pintype "passive"))
      (node (ref "LCC") (pin "2") (pinfunction "2_2") (pintype "passive"))
      (node (ref "ON/OFF") (pin "10") (pinfunction "S_10") (pintype "passive"))
      (node (ref "ON/OFF") (pin "6") (pinfunction "S_6") (pintype "passive"))
      (node (ref "ON/OFF") (pin "8") (pinfunction "S_8") (pintype "passive"))
      (node (ref "Q1") (pin "E") (pinfunction "E_E") (pintype "passive"))
      (node (ref "Q2") (pin "E") (pinfunction "E_E") (pintype "passive"))
      (node (ref "Q3") (pin "E") (pinfunction "E_E") (pintype "passive"))
      (node (ref "Q4") (pin "E") (pinfunction "E_E") (pintype "passive"))
      (node (ref "Q5") (pin "E") (pinfunction "E_E") (pintype "passive"))
      (node (ref "Q6") (pin "E") (pinfunction "E_E") (pintype "passive"))
      (node (ref "Q7") (pin "E") (pinfunction "E_E") (pintype "passive"))
      (node (ref "R12") (pin "1") (pinfunction "1_1") (pintype "passive"))
      (node (ref "R13") (pin "1") (pinfunction "1_1") (pintype "passive"))
      (node (ref "R15") (pin "1") (pinfunction "1_1") (pintype "passive"))
      (node (ref "R18") (pin "1") (pinfunction "1_1") (pintype "passive"))
      (node (ref "R19") (pin "1") (pinfunction "1_1") (pintype "passive"))
      (node (ref "R23") (pin "1") (pinfunction "1_1") (pintype "passive"))
      (node (ref "R25") (pin "1") (pinfunction "1_1") (pintype "passive"))
      (node (ref "R27") (pin "1") (pinfunction "1_1") (pintype "passive"))
      (node (ref "R3") (pin "1") (pinfunction "1_1") (pintype "passive"))
      (node (ref "R31") (pin "1") (pinfunction "1_1") (pintype "passive"))
      (node (ref "R33") (pin "1") (pinfunction "1_1") (pintype "passive"))
      (node (ref "R36") (pin "1") (pinfunction "1_1") (pintype "passive"))
      (node (ref "R38") (pin "1") (pinfunction "1_1") (pintype "passive"))
      (node (ref "R8") (pin "1") (pinfunction "1_1") (pintype "passive"))
      (node (ref "R9") (pin "1") (pinfunction "1_1") (pintype "passive"))
      (node (ref "RB1") (pin "6") (pinfunction "6_6") (pintype "passive"))
      (node (ref "RB2") (pin "1") (pinfunction "1_1") (pintype "passive"))
      (node (ref "RB2") (pin "8") (pinfunction "8_8") (pintype "passive"))
      (node (ref "SACC") (pin "2") (pinfunction "2_2") (pintype "passive"))
      (node (ref "X12") (pin "4") (pinfunction "GND_4") (pintype "power_in"))
    )
    (net (code "67") (name "GYRO_CIN") (class "Default")
      (node (ref "GYRO") (pin "8") (pinfunction "8_8") (pintype "passive"))
    )
    (net (code "68") (name "GYRO_COUT") (class "Default")
      (node (ref "GYRO") (pin "7") (pinfunction "7_7") (pintype "passive"))
    )
    (net (code "69") (name "GYRO_ESC") (class "Default")
      (node (ref "GYRO") (pin "6") (pinfunction "6_6") (pintype "passive"))
    )
    (net (code "70") (name "GYRO_ESD") (class "Default")
      (node (ref "GYRO") (pin "5") (pinfunction "5_5") (pintype "passive"))
    )
    (net (code "71") (name "GYRO_FSYNC") (class "Default")
      (node (ref "GYRO") (pin "10") (pinfunction "10_10") (pintype "passive"))
    )
    (net (code "72") (name "GYRO_INT") (class "Default")
      (node (ref "GYRO_2") (pin "1") (pinfunction "1_1") (pintype "passive"))
    )
    (net (code "73") (name "GYRO_PWR") (class "Default")
      (node (ref "ARD_8") (pin "5") (pinfunction "5_5") (pintype "passive"))
      (node (ref "GYRO") (pin "2") (pinfunction "2_2") (pintype "passive"))
    )
    (net (code "74") (name "HEATER_1_PWR") (class "Default")
      (node (ref "C3_CMD") (pin "8") (pinfunction "8_8") (pintype "passive"))
      (node (ref "H1") (pin "1") (pinfunction "S_1") (pintype "passive"))
      (node (ref "PO4") (pin "1") (pinfunction "P_1") (pintype "passive"))
    )
    (net (code "75") (name "HEATER_1_PWR_RTN") (class "Default")
      (node (ref "C3_CMD") (pin "9") (pinfunction "9_9") (pintype "passive"))
      (node (ref "H1") (pin "2") (pinfunction "S_2") (pintype "passive"))
      (node (ref "Q4") (pin "C") (pinfunction "C_C") (pintype "passive"))
    )
    (net (code "76") (name "HEATER_2_PWR") (class "Default")
      (node (ref "C3_CMD") (pin "10") (pinfunction "10_10") (pintype "passive"))
      (node (ref "H2") (pin "1") (pinfunction "S_1") (pintype "passive"))
      (node (ref "PO5") (pin "1") (pinfunction "P_1") (pintype "passive"))
    )
    (net (code "77") (name "HEATER_2_PWR_RTN") (class "Default")
      (node (ref "C3_CMD") (pin "11") (pinfunction "11_11") (pintype "passive"))
      (node (ref "H2") (pin "2") (pinfunction "S_2") (pintype "passive"))
      (node (ref "Q5") (pin "C") (pinfunction "C_C") (pintype "passive"))
    )
    (net (code "78") (name "HEATER_CONTROL_1") (class "Default")
      (node (ref "ARD_7") (pin "10") (pinfunction "10_10") (pintype "passive"))
      (node (ref "R10") (pin "2") (pinfunction "2_2") (pintype "passive"))
    )
    (net (code "79") (name "HEATER_CONTROL_2") (class "Default")
      (node (ref "ARD_6") (pin "3") (pinfunction "3_3") (pintype "passive"))
      (node (ref "R11") (pin "2") (pinfunction "2_2") (pintype "passive"))
    )
    (net (code "80") (name "IOREF") (class "Default")
      (node (ref "ARD_1") (pin "2") (pinfunction "2_2") (pintype "passive"))
    )
    (net (code "81") (name "LI_ION") (class "Default")
      (node (ref "RB2") (pin "7") (pinfunction "7_7") (pintype "passive"))
    )
    (net (code "82") (name "LOAD_IN") (class "Default")
      (node (ref "D1") (pin "C") (pinfunction "C_C") (pintype "passive"))
      (node (ref "D2") (pin "C") (pinfunction "C_C") (pintype "passive"))
      (node (ref "LCC") (pin "6") (pinfunction "6_6") (pintype "passive"))
    )
    (net (code "83") (name "MISO") (class "Default")
      (node (ref "ARD_4") (pin "1") (pinfunction "1_1") (pintype "passive"))
      (node (ref "ARD_7") (pin "6") (pinfunction "6_6") (pintype "passive"))
    )
    (net (code "84") (name "MOSI") (class "Default")
      (node (ref "ARD_4") (pin "4") (pinfunction "4_4") (pintype "passive"))
      (node (ref "ARD_7") (pin "7") (pinfunction "7_7") (pintype "passive"))
    )
    (net (code "85") (name "NET_AV") (class "Default")
      (node (ref "RB2") (pin "5") (pinfunction "5_5") (pintype "passive"))
    )
    (net (code "86") (name "Net-(B1C-S)") (class "Default")
      (node (ref "B1") (pin "3") (pinfunction "S_3") (pintype "passive"))
      (node (ref "B1_CELL_3") (pin "1") (pinfunction "P_1") (pintype "passive"))
    )
    (net (code "87") (name "Net-(B1D-S)") (class "Default")
      (node (ref "B1") (pin "4") (pinfunction "S_4") (pintype "passive"))
      (node (ref "B1_CELL_2") (pin "1") (pinfunction "P_1") (pintype "passive"))
    )
    (net (code "88") (name "Net-(B1E-S)") (class "Default")
      (node (ref "B1") (pin "5") (pinfunction "S_5") (pintype "passive"))
      (node (ref "B1_CELL_1") (pin "1") (pinfunction "P_1") (pintype "passive"))
    )
    (net (code "89") (name "Net-(B2C-S)") (class "Default")
      (node (ref "B2") (pin "3") (pinfunction "S_3") (pintype "passive"))
      (node (ref "B3_CELL_3") (pin "1") (pinfunction "P_1") (pintype "passive"))
    )
    (net (code "90") (name "Net-(B2D-S)") (class "Default")
      (node (ref "B2") (pin "4") (pinfunction "S_4") (pintype "passive"))
      (node (ref "B2_CELL_2") (pin "1") (pinfunction "P_1") (pintype "passive"))
    )
    (net (code "91") (name "Net-(B2E-S)") (class "Default")
      (node (ref "B2") (pin "5") (pinfunction "S_5") (pintype "passive"))
      (node (ref "B2_CELL_1") (pin "1") (pinfunction "P_1") (pintype "passive"))
    )
    (net (code "92") (name "Net-(Q4-PadB)") (class "Default")
      (node (ref "Q4") (pin "B") (pinfunction "B_B") (pintype "passive"))
      (node (ref "R10") (pin "1") (pinfunction "1_1") (pintype "passive"))
      (node (ref "R12") (pin "2") (pinfunction "2_2") (pintype "passive"))
    )
    (net (code "93") (name "Net-(Q5-PadB)") (class "Default")
      (node (ref "Q5") (pin "B") (pinfunction "B_B") (pintype "passive"))
      (node (ref "R11") (pin "1") (pinfunction "1_1") (pintype "passive"))
      (node (ref "R13") (pin "2") (pinfunction "2_2") (pintype "passive"))
    )
    (net (code "94") (name "Net-(Q6-PadB)") (class "Default")
      (node (ref "Q6") (pin "B") (pinfunction "B_B") (pintype "passive"))
      (node (ref "R16") (pin "1") (pinfunction "1_1") (pintype "passive"))
      (node (ref "R18") (pin "2") (pinfunction "2_2") (pintype "passive"))
    )
    (net (code "95") (name "Net-(Q7-PadB)") (class "Default")
      (node (ref "Q7") (pin "B") (pinfunction "B_B") (pintype "passive"))
      (node (ref "R17") (pin "1") (pinfunction "1_1") (pintype "passive"))
      (node (ref "R19") (pin "2") (pinfunction "2_2") (pintype "passive"))
    )
    (net (code "96") (name "Net-(T1-B)") (class "Default")
      (node (ref "R1") (pin "1") (pinfunction "1_1") (pintype "passive"))
      (node (ref "R2") (pin "2") (pinfunction "2_2") (pintype "passive"))
      (node (ref "T1") (pin "2") (pinfunction "B_2") (pintype "passive"))
    )
    (net (code "97") (name "Net-(T1-E)") (class "Default")
      (node (ref "Q1") (pin "B") (pinfunction "B_B") (pintype "passive"))
      (node (ref "R2") (pin "1") (pinfunction "1_1") (pintype "passive"))
      (node (ref "R3") (pin "2") (pinfunction "2_2") (pintype "passive"))
      (node (ref "T1") (pin "3") (pinfunction "E_3") (pintype "passive"))
    )
    (net (code "98") (name "Net-(T2-B)") (class "Default")
      (node (ref "R4") (pin "1") (pinfunction "1_1") (pintype "passive"))
      (node (ref "R6") (pin "2") (pinfunction "2_2") (pintype "passive"))
      (node (ref "T2") (pin "2") (pinfunction "B_2") (pintype "passive"))
    )
    (net (code "99") (name "Net-(T2-E)") (class "Default")
      (node (ref "Q2") (pin "B") (pinfunction "B_B") (pintype "passive"))
      (node (ref "R6") (pin "1") (pinfunction "1_1") (pintype "passive"))
      (node (ref "R8") (pin "2") (pinfunction "2_2") (pintype "passive"))
      (node (ref "T2") (pin "3") (pinfunction "E_3") (pintype "passive"))
    )
    (net (code "100") (name "Net-(T3-B)") (class "Default")
      (node (ref "R5") (pin "1") (pinfunction "1_1") (pintype "passive"))
      (node (ref "R7") (pin "2") (pinfunction "2_2") (pintype "passive"))
      (node (ref "T3") (pin "2") (pinfunction "B_2") (pintype "passive"))
    )
    (net (code "101") (name "Net-(T3-E)") (class "Default")
      (node (ref "Q3") (pin "B") (pinfunction "B_B") (pintype "passive"))
      (node (ref "R7") (pin "1") (pinfunction "1_1") (pintype "passive"))
      (node (ref "R9") (pin "2") (pinfunction "2_2") (pintype "passive"))
      (node (ref "T3") (pin "3") (pinfunction "E_3") (pintype "passive"))
    )
    (net (code "102") (name "ON_OFF") (class "Default")
      (node (ref "RB2") (pin "6") (pinfunction "6_6") (pintype "passive"))
    )
    (net (code "103") (name "PYRO_1_PWR") (class "Default")
      (node (ref "C3_CMD") (pin "1") (pinfunction "1_1") (pintype "passive"))
      (node (ref "PO1") (pin "1") (pinfunction "P_1") (pintype "passive"))
      (node (ref "PYRO1") (pin "1") (pinfunction "S_1") (pintype "passive"))
    )
    (net (code "104") (name "PYRO_1_PWR_RTN") (class "Default")
      (node (ref "C3_CMD") (pin "2") (pinfunction "2_2") (pintype "passive"))
      (node (ref "PYRO1") (pin "2") (pinfunction "S_2") (pintype "passive"))
      (node (ref "Q1") (pin "C") (pinfunction "C_C") (pintype "passive"))
      (node (ref "T1") (pin "1") (pinfunction "C_1") (pintype "passive"))
    )
    (net (code "105") (name "PYRO_2_PWR") (class "Default")
      (node (ref "C3_CMD") (pin "3") (pinfunction "3_3") (pintype "passive"))
      (node (ref "PO2") (pin "1") (pinfunction "P_1") (pintype "passive"))
      (node (ref "PYRO2") (pin "1") (pinfunction "S_1") (pintype "passive"))
    )
    (net (code "106") (name "PYRO_2_PWR_RTN") (class "Default")
      (node (ref "C3_CMD") (pin "4") (pinfunction "4_4") (pintype "passive"))
      (node (ref "PYRO2") (pin "2") (pinfunction "S_2") (pintype "passive"))
      (node (ref "Q2") (pin "C") (pinfunction "C_C") (pintype "passive"))
      (node (ref "T2") (pin "1") (pinfunction "C_1") (pintype "passive"))
    )
    (net (code "107") (name "RESET") (class "Default")
      (node (ref "ARD_1") (pin "3") (pinfunction "3_3") (pintype "passive"))
      (node (ref "ARD_4") (pin "5") (pinfunction "5_5") (pintype "passive"))
      (node (ref "ON/OFF") (pin "9") (pinfunction "S_9") (pintype "passive"))
    )
    (net (code "108") (name "RF_IN") (class "Default")
      (node (ref "GPS") (pin "2") (pinfunction "2_2") (pintype "passive"))
    )
    (net (code "109") (name "RI") (class "Default")
      (node (ref "RB2") (pin "4") (pinfunction "4_4") (pintype "passive"))
    )
    (net (code "110") (name "RTS") (class "Default")
      (node (ref "RB1") (pin "1") (pinfunction "1_1") (pintype "passive"))
    )
    (net (code "111") (name "RX0") (class "Default")
      (node (ref "ARD_6") (pin "8") (pinfunction "8_8") (pintype "passive"))
      (node (ref "X12") (pin "2") (pinfunction "D-_2") (pintype "bidirectional"))
    )
    (net (code "112") (name "RX1") (class "Default")
      (node (ref "ARD_5") (pin "6") (pinfunction "6_6") (pintype "passive"))
      (node (ref "GPS") (pin "5") (pinfunction "5_5") (pintype "passive"))
    )
    (net (code "113") (name "RX2") (class "Default")
      (node (ref "ARD_5") (pin "4") (pinfunction "4_4") (pintype "passive"))
    )
    (net (code "114") (name "RX3") (class "Default")
      (node (ref "ARD_5") (pin "2") (pinfunction "2_2") (pintype "passive"))
      (node (ref "RB1") (pin "2") (pinfunction "2_2") (pintype "passive"))
    )
    (net (code "115") (name "RXB") (class "Default")
      (node (ref "GPS") (pin "7") (pinfunction "7_7") (pintype "passive"))
    )
    (net (code "116") (name "SCK") (class "Default")
      (node (ref "ARD_4") (pin "3") (pinfunction "3_3") (pintype "passive"))
      (node (ref "ARD_7") (pin "5") (pinfunction "5_5") (pintype "passive"))
    )
    (net (code "117") (name "SCL") (class "Default")
      (node (ref "ARD_5") (pin "8") (pinfunction "8_8") (pintype "passive"))
      (node (ref "B1CC") (pin "3") (pinfunction "3_3") (pintype "passive"))
      (node (ref "B2CC") (pin "3") (pinfunction "3_3") (pintype "passive"))
      (node (ref "GYRO") (pin "4") (pinfunction "4_4") (pintype "passive"))
      (node (ref "LCC") (pin "3") (pinfunction "3_3") (pintype "passive"))
      (node (ref "SACC") (pin "3") (pinfunction "3_3") (pintype "passive"))
    )
    (net (code "118") (name "SCL1") (class "Default")
      (node (ref "ARD_7") (pin "1") (pinfunction "1_1") (pintype "passive"))
    )
    (net (code "119") (name "SDA") (class "Default")
      (node (ref "ARD_5") (pin "7") (pinfunction "7_7") (pintype "passive"))
      (node (ref "B1CC") (pin "4") (pinfunction "4_4") (pintype "passive"))
      (node (ref "B2CC") (pin "4") (pinfunction "4_4") (pintype "passive"))
      (node (ref "GYRO") (pin "3") (pinfunction "3_3") (pintype "passive"))
      (node (ref "LCC") (pin "4") (pinfunction "4_4") (pintype "passive"))
      (node (ref "SACC") (pin "4") (pinfunction "4_4") (pintype "passive"))
    )
    (net (code "120") (name "SDA1") (class "Default")
      (node (ref "ARD_7") (pin "2") (pinfunction "2_2") (pintype "passive"))
    )
    (net (code "121") (name "SPARE_1_PWR") (class "Default")
      (node (ref "C3_CMD") (pin "12") (pinfunction "12_12") (pintype "passive"))
      (node (ref "PO6") (pin "1") (pinfunction "P_1") (pintype "passive"))
      (node (ref "SPRL1") (pin "1") (pinfunction "S_1") (pintype "passive"))
    )
    (net (code "122") (name "SPARE_1_PWR_RTN") (class "Default")
      (node (ref "C3_CMD") (pin "13") (pinfunction "13_13") (pintype "passive"))
      (node (ref "Q6") (pin "C") (pinfunction "C_C") (pintype "passive"))
      (node (ref "SPRL1") (pin "2") (pinfunction "S_2") (pintype "passive"))
    )
    (net (code "123") (name "SPARE_2_PWR") (class "Default")
      (node (ref "C3_CMD") (pin "14") (pinfunction "14_14") (pintype "passive"))
      (node (ref "PO7") (pin "1") (pinfunction "P_1") (pintype "passive"))
      (node (ref "SPRL2") (pin "1") (pinfunction "S_1") (pintype "passive"))
    )
    (net (code "124") (name "SPARE_2_PWR_RTN") (class "Default")
      (node (ref "C3_CMD") (pin "15") (pinfunction "15_15") (pintype "passive"))
      (node (ref "Q7") (pin "C") (pinfunction "C_C") (pintype "passive"))
      (node (ref "SPRL2") (pin "2") (pinfunction "S_2") (pintype "passive"))
    )
    (net (code "125") (name "SPARE_HIGH_1_CONTROL") (class "Default")
      (node (ref "ARD_9") (pin "2") (pinfunction "2_2") (pintype "passive"))
      (node (ref "R5") (pin "2") (pinfunction "2_2") (pintype "passive"))
    )
    (net (code "126") (name "SPARE_HIGH_1_PWR") (class "Default")
      (node (ref "C3_CMD") (pin "5") (pinfunction "5_5") (pintype "passive"))
      (node (ref "PO3") (pin "1") (pinfunction "P_1") (pintype "passive"))
      (node (ref "SPRH1") (pin "1") (pinfunction "S_1") (pintype "passive"))
    )
    (net (code "127") (name "SPARE_HIGH_1_PWR_RTN") (class "Default")
      (node (ref "C3_CMD") (pin "6") (pinfunction "6_6") (pintype "passive"))
      (node (ref "Q3") (pin "C") (pinfunction "C_C") (pintype "passive"))
      (node (ref "SPRH1") (pin "2") (pinfunction "S_2") (pintype "passive"))
      (node (ref "T3") (pin "1") (pinfunction "C_1") (pintype "passive"))
    )
    (net (code "128") (name "SPARE_LOW_1_CONTROL") (class "Default")
      (node (ref "ARD_9") (pin "3") (pinfunction "3_3") (pintype "passive"))
      (node (ref "R16") (pin "2") (pinfunction "2_2") (pintype "passive"))
    )
    (net (code "129") (name "SPARE_LOW_2_CONTROL") (class "Default")
      (node (ref "ARD_9") (pin "4") (pinfunction "4_4") (pintype "passive"))
      (node (ref "R17") (pin "2") (pinfunction "2_2") (pintype "passive"))
    )
    (net (code "130") (name "S{slash}A_PWR_IN") (class "Default")
      (node (ref "C2_PWR") (pin "10") (pinfunction "10_10") (pintype "passive"))
      (node (ref "C2_PWR") (pin "6") (pinfunction "6_6") (pintype "passive"))
      (node (ref "C2_PWR") (pin "8") (pinfunction "8_8") (pintype "passive"))
      (node (ref "SACC") (pin "6") (pinfunction "6_6") (pintype "passive"))
    )
    (net (code "131") (name "S{slash}A_PWR_OUT") (class "Default")
      (node (ref "MPPT") (pin "3") (pinfunction "S_3") (pintype "passive"))
      (node (ref "SACC") (pin "5") (pinfunction "5_5") (pintype "passive"))
    )
    (net (code "132") (name "S{slash}A_PWR_RTN") (class "Default")
      (node (ref "C2_PWR") (pin "11") (pinfunction "11_11") (pintype "passive"))
      (node (ref "C2_PWR") (pin "7") (pinfunction "7_7") (pintype "passive"))
      (node (ref "C2_PWR") (pin "9") (pinfunction "9_9") (pintype "passive"))
      (node (ref "MPPT") (pin "4") (pinfunction "S_4") (pintype "passive"))
    )
    (net (code "133") (name "TEMP_EXT_1") (class "Default")
      (node (ref "ARD_2") (pin "8") (pinfunction "8_8") (pintype "passive"))
      (node (ref "C1_TLM") (pin "1") (pinfunction "1_1") (pintype "passive"))
      (node (ref "R22") (pin "1") (pinfunction "1_1") (pintype "passive"))
      (node (ref "R23") (pin "2") (pinfunction "2_2") (pintype "passive"))
    )
    (net (code "134") (name "TEMP_EXT_2") (class "Default")
      (node (ref "ARD_2") (pin "6") (pinfunction "6_6") (pintype "passive"))
      (node (ref "C1_TLM") (pin "3") (pinfunction "3_3") (pintype "passive"))
      (node (ref "R24") (pin "1") (pinfunction "1_1") (pintype "passive"))
      (node (ref "R25") (pin "2") (pinfunction "2_2") (pintype "passive"))
    )
    (net (code "135") (name "TX0") (class "Default")
      (node (ref "ARD_6") (pin "7") (pinfunction "7_7") (pintype "passive"))
      (node (ref "X12") (pin "3") (pinfunction "D+_3") (pintype "bidirectional"))
    )
    (net (code "136") (name "TX1") (class "Default")
      (node (ref "ARD_5") (pin "5") (pinfunction "5_5") (pintype "passive"))
      (node (ref "GPS") (pin "4") (pinfunction "4_4") (pintype "passive"))
    )
    (net (code "137") (name "TX2") (class "Default")
      (node (ref "ARD_5") (pin "3") (pinfunction "3_3") (pintype "passive"))
    )
    (net (code "138") (name "TX3") (class "Default")
      (node (ref "ARD_5") (pin "1") (pinfunction "1_1") (pintype "passive"))
      (node (ref "RB1") (pin "3") (pinfunction "3_3") (pintype "passive"))
    )
    (net (code "139") (name "TXB") (class "Default")
      (node (ref "GPS") (pin "6") (pinfunction "6_6") (pintype "passive"))
    )
    (net (code "140") (name "UNKNOWN") (class "Default")
      (node (ref "ARD_1") (pin "1") (pinfunction "1_1") (pintype "passive"))
    )
    (net (code "141") (name "VBAT") (class "Default")
      (node (ref "GPS") (pin "3") (pinfunction "3_3") (pintype "passive"))
    )
    (net (code "142") (name "VCC_RB") (class "Default")
      (node (ref "RB1") (pin "4") (pinfunction "4_4") (pintype "passive"))
    )
    (net (code "143") (name "VIN") (class "Default")
      (node (ref "ARD_1") (pin "8") (pinfunction "8_8") (pintype "passive"))
      (node (ref "LCC") (pin "5") (pinfunction "5_5") (pintype "passive"))
      (node (ref "PVIN1") (pin "1") (pinfunction "P_1") (pintype "passive"))
      (node (ref "PVIN2") (pin "1") (pinfunction "P_1") (pintype "passive"))
      (node (ref "PVIN3") (pin "1") (pinfunction "P_1") (pintype "passive"))
      (node (ref "PVIN4") (pin "1") (pinfunction "P_1") (pintype "passive"))
      (node (ref "PVIN5") (pin "1") (pinfunction "P_1") (pintype "passive"))
      (node (ref "PVIN6") (pin "1") (pinfunction "P_1") (pintype "passive"))
      (node (ref "PVIN7") (pin "1") (pinfunction "P_1") (pintype "passive"))
      (node (ref "R14") (pin "2") (pinfunction "2_2") (pintype "passive"))
    )
    (net (code "144") (name "VIN_VOLTAGE_TLM") (class "Default")
      (node (ref "ARD_2") (pin "4") (pinfunction "4_4") (pintype "passive"))
      (node (ref "C1") (pin "1") (pinfunction "1_1") (pintype "passive"))
      (node (ref "R14") (pin "1") (pinfunction "1_1") (pintype "passive"))
      (node (ref "R15") (pin "2") (pinfunction "2_2") (pintype "passive"))
    )
    (net (code "145") (name "unconnected-(ALT-Pad8)") (class "Default")
      (node (ref "ALT") (pin "8") (pinfunction "8_8") (pintype "passive"))
    )
    (net (code "146") (name "unconnected-(B1B-S-Pad2)") (class "Default")
      (node (ref "B1") (pin "2") (pinfunction "S_2") (pintype "passive"))
    )
    (net (code "147") (name "unconnected-(B2B-S-Pad2)") (class "Default")
      (node (ref "B2") (pin "2") (pinfunction "S_2") (pintype "passive"))
    )
    (net (code "148") (name "unconnected-(C1_TLM-Pad5)") (class "Default")
      (node (ref "C1_TLM") (pin "5") (pinfunction "5_5") (pintype "passive"))
    )
    (net (code "149") (name "unconnected-(C1_TLM-Pad6)") (class "Default")
      (node (ref "C1_TLM") (pin "6") (pinfunction "6_6") (pintype "passive"))
    )
    (net (code "150") (name "unconnected-(C1_TLM-Pad7)") (class "Default")
      (node (ref "C1_TLM") (pin "7") (pinfunction "7_7") (pintype "passive"))
    )
    (net (code "151") (name "unconnected-(C1_TLM-Pad8)") (class "Default")
      (node (ref "C1_TLM") (pin "8") (pinfunction "8_8") (pintype "passive"))
    )
    (net (code "152") (name "unconnected-(C1_TLM-Pad9)") (class "Default")
      (node (ref "C1_TLM") (pin "9") (pinfunction "9_9") (pintype "passive"))
    )
    (net (code "153") (name "unconnected-(C1_TLM-Pad10)") (class "Default")
      (node (ref "C1_TLM") (pin "10") (pinfunction "10_10") (pintype "passive"))
    )
    (net (code "154") (name "unconnected-(C1_TLM-Pad11)") (class "Default")
      (node (ref "C1_TLM") (pin "11") (pinfunction "11_11") (pintype "passive"))
    )
    (net (code "155") (name "unconnected-(C1_TLM-Pad12)") (class "Default")
      (node (ref "C1_TLM") (pin "12") (pinfunction "12_12") (pintype "passive"))
    )
    (net (code "156") (name "unconnected-(C1_TLM-Pad13)") (class "Default")
      (node (ref "C1_TLM") (pin "13") (pinfunction "13_13") (pintype "passive"))
    )
    (net (code "157") (name "unconnected-(C1_TLM-Pad14)") (class "Default")
      (node (ref "C1_TLM") (pin "14") (pinfunction "14_14") (pintype "passive"))
    )
    (net (code "158") (name "unconnected-(C1_TLM-Pad15)") (class "Default")
      (node (ref "C1_TLM") (pin "15") (pinfunction "15_15") (pintype "passive"))
    )
    (net (code "159") (name "unconnected-(C2_PWR-Pad5)") (class "Default")
      (node (ref "C2_PWR") (pin "5") (pinfunction "5_5") (pintype "passive"))
    )
    (net (code "160") (name "unconnected-(C2_PWR-Pad12)") (class "Default")
      (node (ref "C2_PWR") (pin "12") (pinfunction "12_12") (pintype "passive"))
    )
    (net (code "161") (name "unconnected-(C2_PWR-Pad13)") (class "Default")
      (node (ref "C2_PWR") (pin "13") (pinfunction "13_13") (pintype "passive"))
    )
    (net (code "162") (name "unconnected-(C2_PWR-Pad14)") (class "Default")
      (node (ref "C2_PWR") (pin "14") (pinfunction "14_14") (pintype "passive"))
    )
    (net (code "163") (name "unconnected-(C2_PWR-Pad15)") (class "Default")
      (node (ref "C2_PWR") (pin "15") (pinfunction "15_15") (pintype "passive"))
    )
    (net (code "164") (name "unconnected-(C3_CMD-Pad7)") (class "Default")
      (node (ref "C3_CMD") (pin "7") (pinfunction "7_7") (pintype "passive"))
    )
  )
)
